# Punk_Console.net
KiCad netlist of a schematic drawn in EAGLE
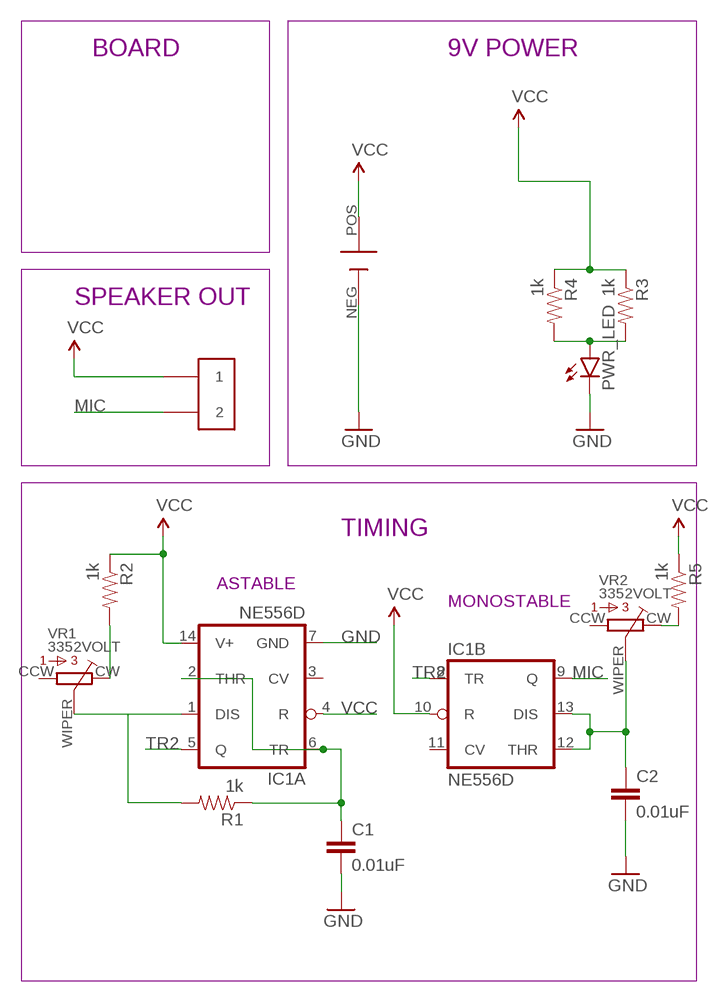
[diagram p0: schematic, sheet 1]

(export (version "E")
  (design (tool "Eeschema 10.0.6"))
  (components
    (comp (ref "C1")
      (value "0.01uF")
      (footprint "eagle-import:1206")
      (libsource (lib "eagle-import") (part "CAP1206"))
    )
    (comp (ref "C2")
      (value "0.01uF")
      (footprint "eagle-import:1206")
      (libsource (lib "eagle-import") (part "CAP1206"))
    )
    (comp (ref "IC1")
      (value "NE556D")
      (footprint "eagle-import:SO14")
      (libsource (lib "eagle-import") (part "556DNE"))
    )
    (comp (ref "PWR_LED")
      (value "LED1206")
      (footprint "eagle-import:LED-1206")
      (libsource (lib "eagle-import") (part "LED1206"))
    )
    (comp (ref "R1")
      (value "1k")
      (footprint "eagle-import:1206")
      (libsource (lib "eagle-import") (part "RESISTOR1206"))
    )
    (comp (ref "R2")
      (value "1k")
      (footprint "eagle-import:1206")
      (libsource (lib "eagle-import") (part "RESISTOR1206"))
    )
    (comp (ref "R3")
      (value "1k")
      (footprint "eagle-import:1206")
      (libsource (lib "eagle-import") (part "RESISTOR1206"))
    )
    (comp (ref "R4")
      (value "1k")
      (footprint "eagle-import:1206")
      (libsource (lib "eagle-import") (part "RESISTOR1206"))
    )
    (comp (ref "R5")
      (value "1k")
      (footprint "eagle-import:1206")
      (libsource (lib "eagle-import") (part "RESISTOR1206"))
    )
    (comp (ref "U$4")
      (value "SMD_BATTERY_9VVIA")
      (footprint "eagle-import:VIA_BATTERY_PADS")
      (libsource (lib "eagle-import") (part "SMD_BATTERY_9VVIA"))
    )
    (comp (ref "U$5")
      (value "BUZZER")
      (footprint "eagle-import:BUZZER_PS1240P02BT")
      (libsource (lib "eagle-import") (part "BUZZER"))
    )
    (comp (ref "VR1")
      (value "3352VOLT")
      (footprint "eagle-import:3352E_VOLT_VIA")
      (libsource (lib "eagle-import") (part "3352VOLT"))
    )
    (comp (ref "VR2")
      (value "3352VOLT")
      (footprint "eagle-import:3352E_VOLT_VIA")
      (libsource (lib "eagle-import") (part "3352VOLT"))
    )
  )
  (nets
    (net (code "1") (name "/MIC") (class "Default")
      (node (ref "IC1") (pin "9") (pinfunction "Q_9") (pintype "output"))
      (node (ref "U$5") (pin "P$2") (pinfunction "2_P$2") (pintype "bidirectional"))
    )
    (net (code "2") (name "/TR2") (class "Default")
      (node (ref "IC1") (pin "5") (pinfunction "Q_5") (pintype "output"))
      (node (ref "IC1") (pin "8") (pinfunction "TR_8") (pintype "input"))
    )
    (net (code "3") (name "GND") (class "Default")
      (node (ref "C1") (pin "2") (pinfunction "2_2") (pintype "passive"))
      (node (ref "C2") (pin "2") (pinfunction "2_2") (pintype "passive"))
      (node (ref "IC1") (pin "7") (pinfunction "GND_7") (pintype "power_in"))
      (node (ref "PWR_LED") (pin "C") (pinfunction "C_C") (pintype "passive"))
      (node (ref "U$4") (pin "NEG") (pinfunction "NEG_NEG") (pintype "bidirectional"))
    )
    (net (code "4") (name "Net-(IC1A-DIS)") (class "Default")
      (node (ref "IC1") (pin "1") (pinfunction "DIS_1") (pintype "input"))
      (node (ref "R1") (pin "2") (pinfunction "2_2") (pintype "passive"))
      (node (ref "VR1") (pin "WIPER") (pinfunction "2_WIPER") (pintype "passive"))
    )
    (net (code "5") (name "Net-(IC1A-THR)") (class "Default")
      (node (ref "C1") (pin "1") (pinfunction "1_1") (pintype "passive"))
      (node (ref "IC1") (pin "2") (pinfunction "THR_2") (pintype "input"))
      (node (ref "IC1") (pin "6") (pinfunction "TR_6") (pintype "input"))
      (node (ref "R1") (pin "1") (pinfunction "1_1") (pintype "passive"))
    )
    (net (code "6") (name "Net-(IC1B-DIS)") (class "Default")
      (node (ref "C2") (pin "1") (pinfunction "1_1") (pintype "passive"))
      (node (ref "IC1") (pin "12") (pinfunction "THR_12") (pintype "input"))
      (node (ref "IC1") (pin "13") (pinfunction "DIS_13") (pintype "input"))
      (node (ref "VR2") (pin "WIPER") (pinfunction "2_WIPER") (pintype "passive"))
    )
    (net (code "7") (name "Net-(PWR_LED-PadA)") (class "Default")
      (node (ref "PWR_LED") (pin "A") (pinfunction "A_A") (pintype "passive"))
      (node (ref "R3") (pin "2") (pinfunction "2_2") (pintype "passive"))
      (node (ref "R4") (pin "2") (pinfunction "2_2") (pintype "passive"))
    )
    (net (code "8") (name "Net-(VR1-3)") (class "Default")
      (node (ref "R2") (pin "2") (pinfunction "2_2") (pintype "passive"))
      (node (ref "VR1") (pin "CW") (pinfunction "3_CW") (pintype "passive"))
    )
    (net (code "9") (name "Net-(VR2-3)") (class "Default")
      (node (ref "R5") (pin "2") (pinfunction "2_2") (pintype "passive"))
      (node (ref "VR2") (pin "CW") (pinfunction "3_CW") (pintype "passive"))
    )
    (net (code "10") (name "VCC") (class "Default")
      (node (ref "IC1") (pin "10") (pinfunction "R_10") (pintype "input"))
      (node (ref "IC1") (pin "14") (pinfunction "V+_14") (pintype "power_in"))
      (node (ref "IC1") (pin "4") (pinfunction "R_4") (pintype "input"))
      (node (ref "R2") (pin "1") (pinfunction "1_1") (pintype "passive"))
      (node (ref "R3") (pin "1") (pinfunction "1_1") (pintype "passive"))
      (node (ref "R4") (pin "1") (pinfunction "1_1") (pintype "passive"))
      (node (ref "R5") (pin "1") (pinfunction "1_1") (pintype "passive"))
      (node (ref "U$4") (pin "POS") (pinfunction "POS_POS") (pintype "bidirectional"))
      (node (ref "U$5") (pin "P$1") (pinfunction "1_P$1") (pintype "bidirectional"))
    )
    (net (code "11") (name "unconnected-(IC1A-CV-Pad3)") (class "Default")
      (node (ref "IC1") (pin "3") (pinfunction "CV_3") (pintype "input"))
    )
    (net (code "12") (name "unconnected-(IC1B-CV-Pad11)") (class "Default")
      (node (ref "IC1") (pin "11") (pinfunction "CV_11") (pintype "input"))
    )
    (net (code "13") (name "unconnected-(VR1-1-PadCCW)") (class "Default")
      (node (ref "VR1") (pin "CCW") (pinfunction "1_CCW") (pintype "passive"))
    )
    (net (code "14") (name "unconnected-(VR2-1-PadCCW)") (class "Default")
      (node (ref "VR2") (pin "CCW") (pinfunction "1_CCW") (pintype "passive"))
    )
  )
)
